# Affichages.net
KiCad netlist of a schematic drawn in Altium Designer
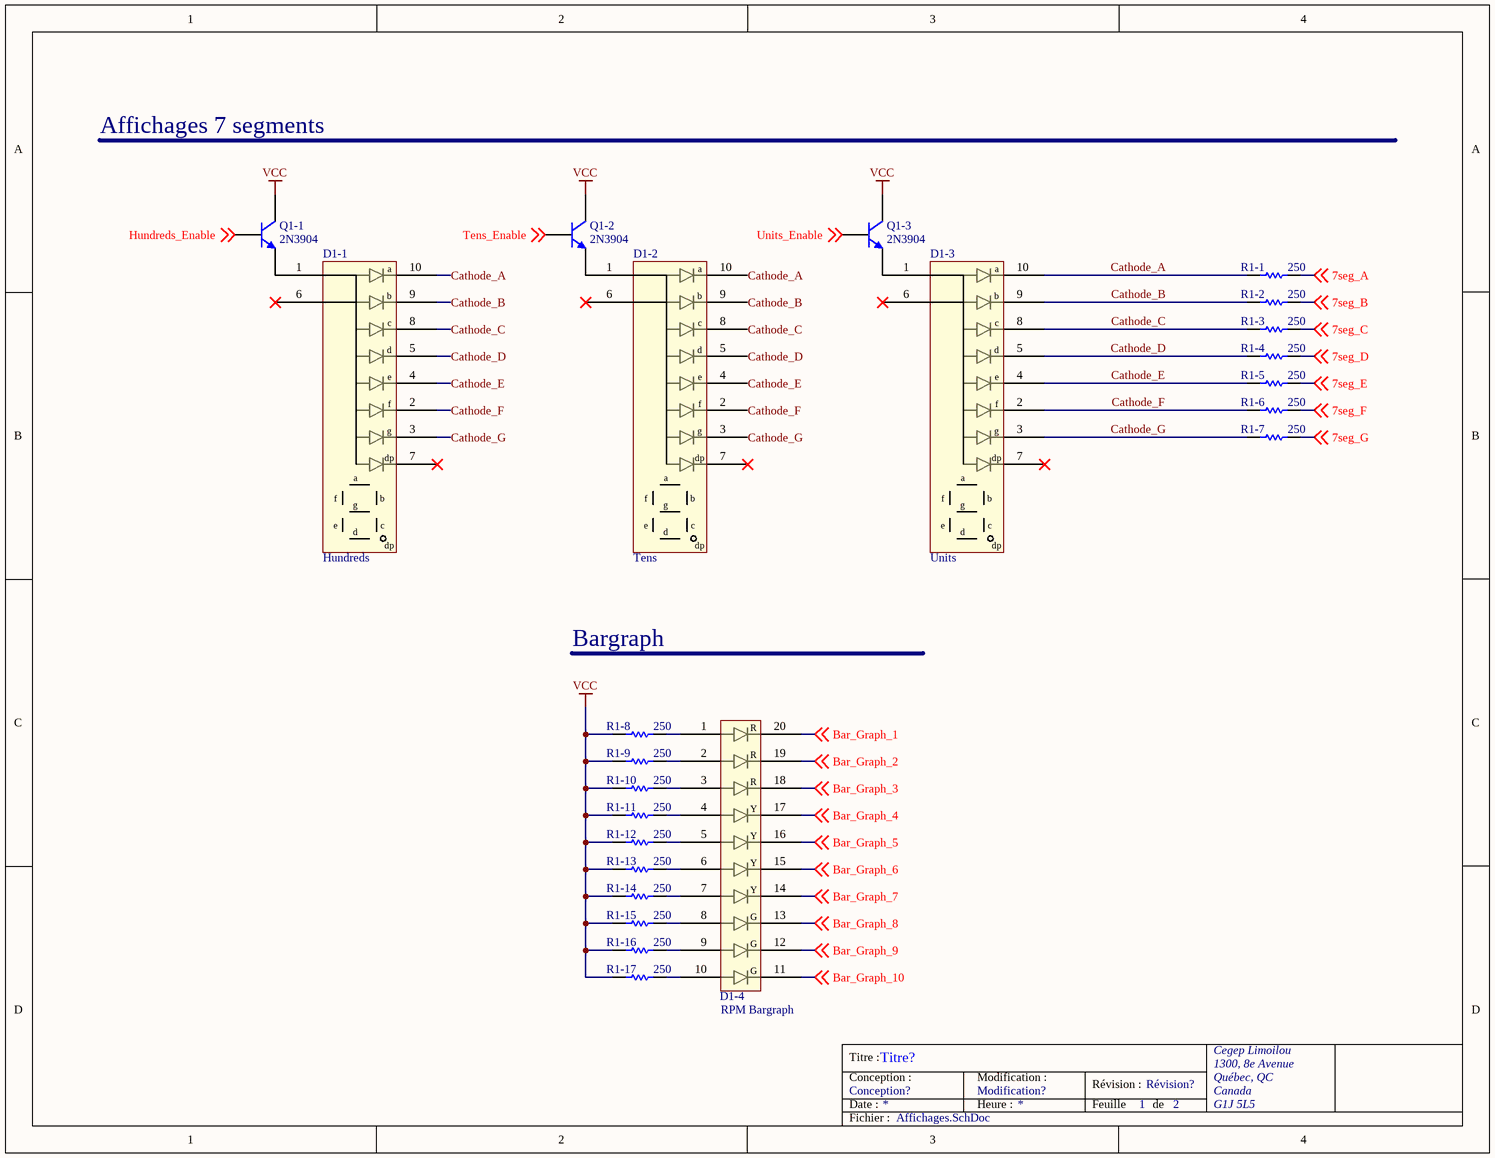
[diagram p0: Affichages.SchDoc]

(export (version "E")
  (design (tool "Eeschema 10.0.6"))
  (components
    (comp (ref "D1-1")
      (value "Hundreds")
      (footprint "LED_7SEG_LSHD-A101")
      (description "LED 7 segment display")
      (fields (field (name "MFG") "Lite-On"))
      (libsource (lib "LibEtudiants") (part "LED_7SEG_LSHD-A101"))
    )
    (comp (ref "D1-2")
      (value "Tens")
      (footprint "LED_7SEG_LSHD-A101")
      (description "LED 7 segment display")
      (fields (field (name "MFG") "Lite-On"))
      (libsource (lib "LibEtudiants") (part "LED_7SEG_LSHD-A101"))
    )
    (comp (ref "D1-3")
      (value "Units")
      (footprint "LED_7SEG_LSHD-A101")
      (description "LED 7 segment display")
      (fields (field (name "MFG") "Lite-On"))
      (libsource (lib "LibEtudiants") (part "LED_7SEG_LSHD-A101"))
    )
    (comp (ref "D1-4")
      (value "RPM Bargraph")
      (footprint "LED_BARGRAPH-HDSP-4832")
      (description "LED bargraph")
      (fields (field (name "MFG") "Broadcom"))
      (libsource (lib "LibEtudiants") (part "LED_BARGRAPH_HDSP-4832"))
    )
    (comp (ref "Q1-1")
      (value "2N3904")
      (footprint "TO-92A")
      (description "NPN General Purpose Amplifier")
      (fields (field (name "PUBLISHER") "Altium Limited"))
      (libsource (lib "Miscellaneous Devices") (part "2N3904"))
    )
    (comp (ref "Q1-2")
      (value "2N3904")
      (footprint "TO-92A")
      (description "NPN General Purpose Amplifier")
      (fields (field (name "PUBLISHER") "Altium Limited"))
      (libsource (lib "Miscellaneous Devices") (part "2N3904"))
    )
    (comp (ref "Q1-3")
      (value "2N3904")
      (footprint "TO-92A")
      (description "NPN General Purpose Amplifier")
      (fields (field (name "PUBLISHER") "Altium Limited"))
      (libsource (lib "Miscellaneous Devices") (part "2N3904"))
    )
    (comp (ref "R1-1")
      (value "250")
      (footprint "AXIAL-0.3")
      (description "Resistor")
      (fields (field (name "Comment") "Res1") (field (name "PUBLISHER") "Altium Limited"))
      (libsource (lib "Miscellaneous Devices") (part "Res1"))
    )
    (comp (ref "R1-2")
      (value "250")
      (footprint "AXIAL-0.3")
      (description "Resistor")
      (fields (field (name "Comment") "Res1") (field (name "PUBLISHER") "Altium Limited"))
      (libsource (lib "Miscellaneous Devices") (part "Res1"))
    )
    (comp (ref "R1-3")
      (value "250")
      (footprint "AXIAL-0.3")
      (description "Resistor")
      (fields (field (name "Comment") "Res1") (field (name "PUBLISHER") "Altium Limited"))
      (libsource (lib "Miscellaneous Devices") (part "Res1"))
    )
    (comp (ref "R1-4")
      (value "250")
      (footprint "AXIAL-0.3")
      (description "Resistor")
      (fields (field (name "Comment") "Res1") (field (name "PUBLISHER") "Altium Limited"))
      (libsource (lib "Miscellaneous Devices") (part "Res1"))
    )
    (comp (ref "R1-5")
      (value "250")
      (footprint "AXIAL-0.3")
      (description "Resistor")
      (fields (field (name "Comment") "Res1") (field (name "PUBLISHER") "Altium Limited"))
      (libsource (lib "Miscellaneous Devices") (part "Res1"))
    )
    (comp (ref "R1-6")
      (value "250")
      (footprint "AXIAL-0.3")
      (description "Resistor")
      (fields (field (name "Comment") "Res1") (field (name "PUBLISHER") "Altium Limited"))
      (libsource (lib "Miscellaneous Devices") (part "Res1"))
    )
    (comp (ref "R1-7")
      (value "250")
      (footprint "AXIAL-0.3")
      (description "Resistor")
      (fields (field (name "Comment") "Res1") (field (name "PUBLISHER") "Altium Limited"))
      (libsource (lib "Miscellaneous Devices") (part "Res1"))
    )
    (comp (ref "R1-8")
      (value "250")
      (footprint "AXIAL-0.3")
      (description "Resistor")
      (fields (field (name "Comment") "Res1") (field (name "PUBLISHER") "Altium Limited"))
      (libsource (lib "Miscellaneous Devices") (part "Res1"))
    )
    (comp (ref "R1-9")
      (value "250")
      (footprint "AXIAL-0.3")
      (description "Resistor")
      (fields (field (name "Comment") "Res1") (field (name "PUBLISHER") "Altium Limited"))
      (libsource (lib "Miscellaneous Devices") (part "Res1"))
    )
    (comp (ref "R1-10")
      (value "250")
      (footprint "AXIAL-0.3")
      (description "Resistor")
      (fields (field (name "Comment") "Res1") (field (name "PUBLISHER") "Altium Limited"))
      (libsource (lib "Miscellaneous Devices") (part "Res1"))
    )
    (comp (ref "R1-11")
      (value "250")
      (footprint "AXIAL-0.3")
      (description "Resistor")
      (fields (field (name "Comment") "Res1") (field (name "PUBLISHER") "Altium Limited"))
      (libsource (lib "Miscellaneous Devices") (part "Res1"))
    )
    (comp (ref "R1-12")
      (value "250")
      (footprint "AXIAL-0.3")
      (description "Resistor")
      (fields (field (name "Comment") "Res1") (field (name "PUBLISHER") "Altium Limited"))
      (libsource (lib "Miscellaneous Devices") (part "Res1"))
    )
    (comp (ref "R1-13")
      (value "250")
      (footprint "AXIAL-0.3")
      (description "Resistor")
      (fields (field (name "Comment") "Res1") (field (name "PUBLISHER") "Altium Limited"))
      (libsource (lib "Miscellaneous Devices") (part "Res1"))
    )
    (comp (ref "R1-14")
      (value "250")
      (footprint "AXIAL-0.3")
      (description "Resistor")
      (fields (field (name "Comment") "Res1") (field (name "PUBLISHER") "Altium Limited"))
      (libsource (lib "Miscellaneous Devices") (part "Res1"))
    )
    (comp (ref "R1-15")
      (value "250")
      (footprint "AXIAL-0.3")
      (description "Resistor")
      (fields (field (name "Comment") "Res1") (field (name "PUBLISHER") "Altium Limited"))
      (libsource (lib "Miscellaneous Devices") (part "Res1"))
    )
    (comp (ref "R1-16")
      (value "250")
      (footprint "AXIAL-0.3")
      (description "Resistor")
      (fields (field (name "Comment") "Res1") (field (name "PUBLISHER") "Altium Limited"))
      (libsource (lib "Miscellaneous Devices") (part "Res1"))
    )
    (comp (ref "R1-17")
      (value "250")
      (footprint "AXIAL-0.3")
      (description "Resistor")
      (fields (field (name "Comment") "Res1") (field (name "PUBLISHER") "Altium Limited"))
      (libsource (lib "Miscellaneous Devices") (part "Res1"))
    )
  )
  (nets
    (net (code "1") (name "/Cathode_A") (class "Default")
      (node (ref "D1-1") (pin "10") (pinfunction "K_A_10") (pintype "passive"))
      (node (ref "D1-2") (pin "10") (pinfunction "K_A_10") (pintype "passive"))
      (node (ref "D1-3") (pin "10") (pinfunction "K_A_10") (pintype "passive"))
      (node (ref "R1-1") (pin "1") (pinfunction "1_1") (pintype "passive"))
    )
    (net (code "2") (name "/Cathode_B") (class "Default")
      (node (ref "D1-1") (pin "9") (pinfunction "K_B_9") (pintype "passive"))
      (node (ref "D1-2") (pin "9") (pinfunction "K_B_9") (pintype "passive"))
      (node (ref "D1-3") (pin "9") (pinfunction "K_B_9") (pintype "passive"))
      (node (ref "R1-2") (pin "1") (pinfunction "1_1") (pintype "passive"))
    )
    (net (code "3") (name "/Cathode_C") (class "Default")
      (node (ref "D1-1") (pin "8") (pinfunction "K_C_8") (pintype "passive"))
      (node (ref "D1-2") (pin "8") (pinfunction "K_C_8") (pintype "passive"))
      (node (ref "D1-3") (pin "8") (pinfunction "K_C_8") (pintype "passive"))
      (node (ref "R1-3") (pin "1") (pinfunction "1_1") (pintype "passive"))
    )
    (net (code "4") (name "/Cathode_D") (class "Default")
      (node (ref "D1-1") (pin "5") (pinfunction "K_D_5") (pintype "passive"))
      (node (ref "D1-2") (pin "5") (pinfunction "K_D_5") (pintype "passive"))
      (node (ref "D1-3") (pin "5") (pinfunction "K_D_5") (pintype "passive"))
      (node (ref "R1-4") (pin "1") (pinfunction "1_1") (pintype "passive"))
    )
    (net (code "5") (name "/Cathode_E") (class "Default")
      (node (ref "D1-1") (pin "4") (pinfunction "K_E_4") (pintype "passive"))
      (node (ref "D1-2") (pin "4") (pinfunction "K_E_4") (pintype "passive"))
      (node (ref "D1-3") (pin "4") (pinfunction "K_E_4") (pintype "passive"))
      (node (ref "R1-5") (pin "1") (pinfunction "1_1") (pintype "passive"))
    )
    (net (code "6") (name "/Cathode_F") (class "Default")
      (node (ref "D1-1") (pin "2") (pinfunction "K_F_2") (pintype "passive"))
      (node (ref "D1-2") (pin "2") (pinfunction "K_F_2") (pintype "passive"))
      (node (ref "D1-3") (pin "2") (pinfunction "K_F_2") (pintype "passive"))
      (node (ref "R1-6") (pin "1") (pinfunction "1_1") (pintype "passive"))
    )
    (net (code "7") (name "/Cathode_G") (class "Default")
      (node (ref "D1-1") (pin "3") (pinfunction "K_G_3") (pintype "passive"))
      (node (ref "D1-2") (pin "3") (pinfunction "K_G_3") (pintype "passive"))
      (node (ref "D1-3") (pin "3") (pinfunction "K_G_3") (pintype "passive"))
      (node (ref "R1-7") (pin "1") (pinfunction "1_1") (pintype "passive"))
    )
    (net (code "8") (name "7seg_A") (class "Default")
      (node (ref "R1-1") (pin "2") (pinfunction "2_2") (pintype "passive"))
    )
    (net (code "9") (name "7seg_B") (class "Default")
      (node (ref "R1-2") (pin "2") (pinfunction "2_2") (pintype "passive"))
    )
    (net (code "10") (name "7seg_C") (class "Default")
      (node (ref "R1-3") (pin "2") (pinfunction "2_2") (pintype "passive"))
    )
    (net (code "11") (name "7seg_D") (class "Default")
      (node (ref "R1-4") (pin "2") (pinfunction "2_2") (pintype "passive"))
    )
    (net (code "12") (name "7seg_E") (class "Default")
      (node (ref "R1-5") (pin "2") (pinfunction "2_2") (pintype "passive"))
    )
    (net (code "13") (name "7seg_F") (class "Default")
      (node (ref "R1-6") (pin "2") (pinfunction "2_2") (pintype "passive"))
    )
    (net (code "14") (name "7seg_G") (class "Default")
      (node (ref "R1-7") (pin "2") (pinfunction "2_2") (pintype "passive"))
    )
    (net (code "15") (name "Bar_Graph_1") (class "Default")
      (node (ref "D1-4") (pin "20") (pinfunction "K_A_20") (pintype "passive"))
    )
    (net (code "16") (name "Bar_Graph_2") (class "Default")
      (node (ref "D1-4") (pin "19") (pinfunction "K_B_19") (pintype "passive"))
    )
    (net (code "17") (name "Bar_Graph_3") (class "Default")
      (node (ref "D1-4") (pin "18") (pinfunction "K_C_18") (pintype "passive"))
    )
    (net (code "18") (name "Bar_Graph_4") (class "Default")
      (node (ref "D1-4") (pin "17") (pinfunction "K_D_17") (pintype "passive"))
    )
    (net (code "19") (name "Bar_Graph_5") (class "Default")
      (node (ref "D1-4") (pin "16") (pinfunction "K_E_16") (pintype "passive"))
    )
    (net (code "20") (name "Bar_Graph_6") (class "Default")
      (node (ref "D1-4") (pin "15") (pinfunction "K_F_15") (pintype "passive"))
    )
    (net (code "21") (name "Bar_Graph_7") (class "Default")
      (node (ref "D1-4") (pin "14") (pinfunction "K_G_14") (pintype "passive"))
    )
    (net (code "22") (name "Bar_Graph_8") (class "Default")
      (node (ref "D1-4") (pin "13") (pinfunction "K_H_13") (pintype "passive"))
    )
    (net (code "23") (name "Bar_Graph_9") (class "Default")
      (node (ref "D1-4") (pin "12") (pinfunction "K_I_12") (pintype "passive"))
    )
    (net (code "24") (name "Bar_Graph_10") (class "Default")
      (node (ref "D1-4") (pin "11") (pinfunction "K_J_11") (pintype "passive"))
    )
    (net (code "25") (name "Hundreds_Enable") (class "Default")
      (node (ref "Q1-1") (pin "2") (pinfunction "B_2") (pintype "passive"))
    )
    (net (code "26") (name "Net-(D1-4-AN_A)") (class "Default")
      (node (ref "D1-4") (pin "1") (pinfunction "AN_A_1") (pintype "passive"))
      (node (ref "R1-8") (pin "1") (pinfunction "1_1") (pintype "passive"))
    )
    (net (code "27") (name "Net-(D1-4-AN_B)") (class "Default")
      (node (ref "D1-4") (pin "2") (pinfunction "AN_B_2") (pintype "passive"))
      (node (ref "R1-9") (pin "1") (pinfunction "1_1") (pintype "passive"))
    )
    (net (code "28") (name "Net-(D1-4-AN_C)") (class "Default")
      (node (ref "D1-4") (pin "3") (pinfunction "AN_C_3") (pintype "passive"))
      (node (ref "R1-10") (pin "1") (pinfunction "1_1") (pintype "passive"))
    )
    (net (code "29") (name "Net-(D1-4-AN_D)") (class "Default")
      (node (ref "D1-4") (pin "4") (pinfunction "AN_D_4") (pintype "passive"))
      (node (ref "R1-11") (pin "1") (pinfunction "1_1") (pintype "passive"))
    )
    (net (code "30") (name "Net-(D1-4-AN_E)") (class "Default")
      (node (ref "D1-4") (pin "5") (pinfunction "AN_E_5") (pintype "passive"))
      (node (ref "R1-12") (pin "1") (pinfunction "1_1") (pintype "passive"))
    )
    (net (code "31") (name "Net-(D1-4-AN_F)") (class "Default")
      (node (ref "D1-4") (pin "6") (pinfunction "AN_F_6") (pintype "passive"))
      (node (ref "R1-13") (pin "1") (pinfunction "1_1") (pintype "passive"))
    )
    (net (code "32") (name "Net-(D1-4-AN_G)") (class "Default")
      (node (ref "D1-4") (pin "7") (pinfunction "AN_G_7") (pintype "passive"))
      (node (ref "R1-14") (pin "1") (pinfunction "1_1") (pintype "passive"))
    )
    (net (code "33") (name "Net-(D1-4-AN_H)") (class "Default")
      (node (ref "D1-4") (pin "8") (pinfunction "AN_H_8") (pintype "passive"))
      (node (ref "R1-15") (pin "1") (pinfunction "1_1") (pintype "passive"))
    )
    (net (code "34") (name "Net-(D1-4-AN_I)") (class "Default")
      (node (ref "D1-4") (pin "9") (pinfunction "AN_I_9") (pintype "passive"))
      (node (ref "R1-16") (pin "1") (pinfunction "1_1") (pintype "passive"))
    )
    (net (code "35") (name "Net-(D1-4-AN_J)") (class "Default")
      (node (ref "D1-4") (pin "10") (pinfunction "AN_J_10") (pintype "passive"))
      (node (ref "R1-17") (pin "1") (pinfunction "1_1") (pintype "passive"))
    )
    (net (code "36") (name "Net-(Q1-1-E)") (class "Default")
      (node (ref "D1-1") (pin "1") (pinfunction "ANODE_1") (pintype "passive"))
      (node (ref "Q1-1") (pin "1") (pinfunction "E_1") (pintype "passive"))
    )
    (net (code "37") (name "Net-(Q1-2-E)") (class "Default")
      (node (ref "D1-2") (pin "1") (pinfunction "ANODE_1") (pintype "passive"))
      (node (ref "Q1-2") (pin "1") (pinfunction "E_1") (pintype "passive"))
    )
    (net (code "38") (name "Net-(Q1-3-E)") (class "Default")
      (node (ref "D1-3") (pin "1") (pinfunction "ANODE_1") (pintype "passive"))
      (node (ref "Q1-3") (pin "1") (pinfunction "E_1") (pintype "passive"))
    )
    (net (code "39") (name "Tens_Enable") (class "Default")
      (node (ref "Q1-2") (pin "2") (pinfunction "B_2") (pintype "passive"))
    )
    (net (code "40") (name "Units_Enable") (class "Default")
      (node (ref "Q1-3") (pin "2") (pinfunction "B_2") (pintype "passive"))
    )
    (net (code "41") (name "VCC") (class "Default")
      (node (ref "Q1-1") (pin "3") (pinfunction "C_3") (pintype "passive"))
      (node (ref "Q1-2") (pin "3") (pinfunction "C_3") (pintype "passive"))
      (node (ref "Q1-3") (pin "3") (pinfunction "C_3") (pintype "passive"))
      (node (ref "R1-10") (pin "2") (pinfunction "2_2") (pintype "passive"))
      (node (ref "R1-11") (pin "2") (pinfunction "2_2") (pintype "passive"))
      (node (ref "R1-12") (pin "2") (pinfunction "2_2") (pintype "passive"))
      (node (ref "R1-13") (pin "2") (pinfunction "2_2") (pintype "passive"))
      (node (ref "R1-14") (pin "2") (pinfunction "2_2") (pintype "passive"))
      (node (ref "R1-15") (pin "2") (pinfunction "2_2") (pintype "passive"))
      (node (ref "R1-16") (pin "2") (pinfunction "2_2") (pintype "passive"))
      (node (ref "R1-17") (pin "2") (pinfunction "2_2") (pintype "passive"))
      (node (ref "R1-8") (pin "2") (pinfunction "2_2") (pintype "passive"))
      (node (ref "R1-9") (pin "2") (pinfunction "2_2") (pintype "passive"))
    )
    (net (code "42") (name "unconnected-(D1-1-ANODE-Pad6)") (class "Default")
      (node (ref "D1-1") (pin "6") (pinfunction "ANODE_6") (pintype "passive+no_connect"))
    )
    (net (code "43") (name "unconnected-(D1-1-K_H-Pad7)") (class "Default")
      (node (ref "D1-1") (pin "7") (pinfunction "K_H_7") (pintype "passive+no_connect"))
    )
    (net (code "44") (name "unconnected-(D1-2-ANODE-Pad6)") (class "Default")
      (node (ref "D1-2") (pin "6") (pinfunction "ANODE_6") (pintype "passive+no_connect"))
    )
    (net (code "45") (name "unconnected-(D1-2-K_H-Pad7)") (class "Default")
      (node (ref "D1-2") (pin "7") (pinfunction "K_H_7") (pintype "passive+no_connect"))
    )
    (net (code "46") (name "unconnected-(D1-3-ANODE-Pad6)") (class "Default")
      (node (ref "D1-3") (pin "6") (pinfunction "ANODE_6") (pintype "passive+no_connect"))
    )
    (net (code "47") (name "unconnected-(D1-3-K_H-Pad7)") (class "Default")
      (node (ref "D1-3") (pin "7") (pinfunction "K_H_7") (pintype "passive+no_connect"))
    )
  )
)
